# TNY275_REMOTE_677.net
KiCad netlist of a schematic drawn in Altium Designer
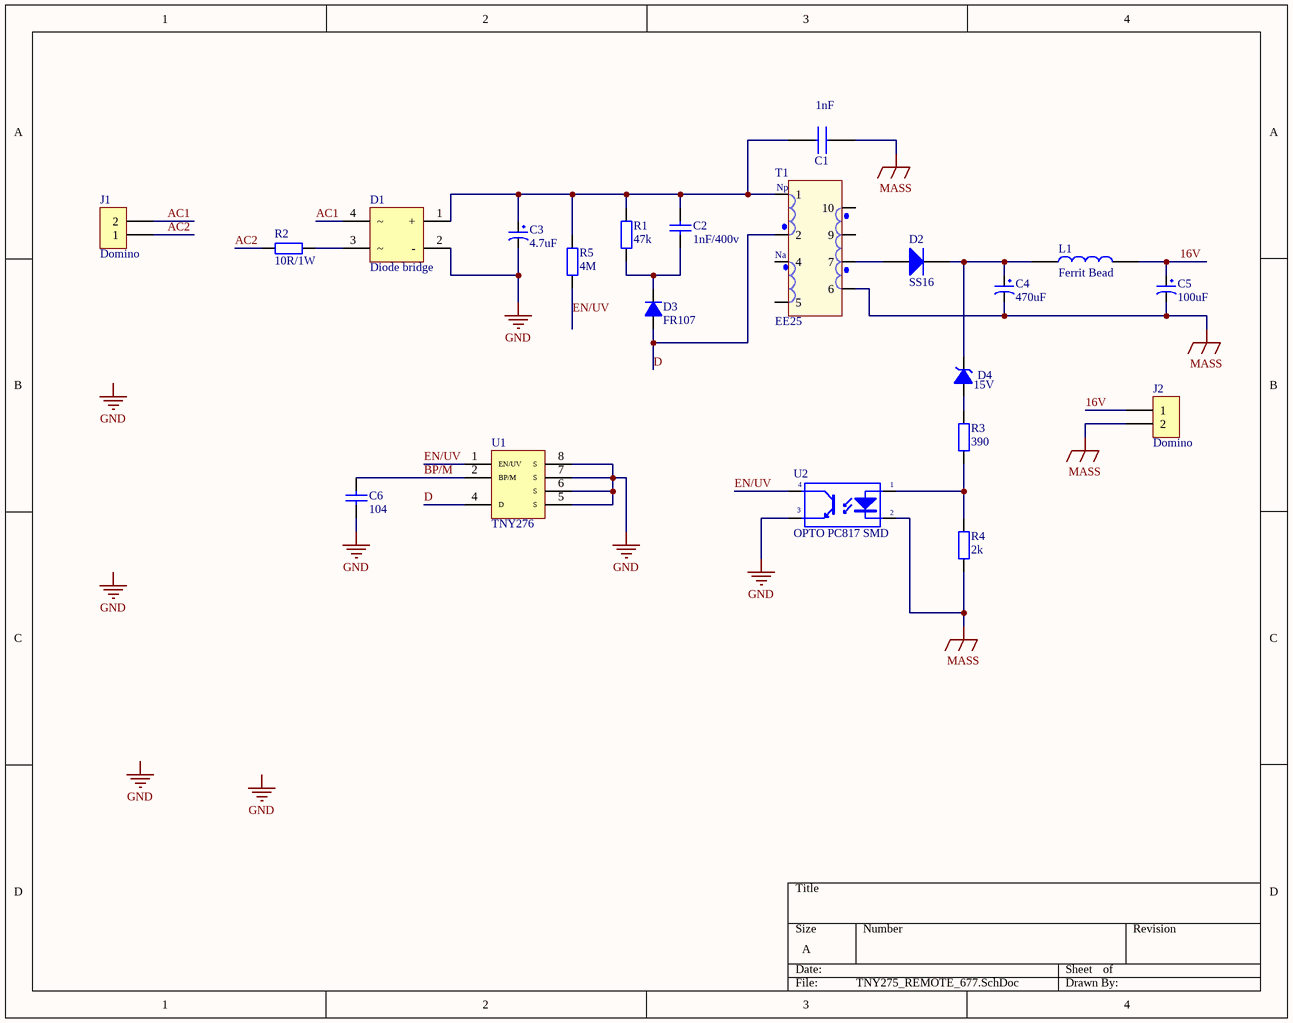
[diagram p0: TNY275_REMOTE_677.SchDoc]

(export (version "E")
  (design (tool "Eeschema 10.0.6"))
  (components
    (comp (ref "C1")
      (value "1nF")
      (footprint "toan:Tenta capacitor")
      (description "...nF +/-10% 275VAC 15 Through Hole Suppression Capacitors")
      (fields (field (name "MANUFACTURER_PART_NUMBER") "MEX104K275A"))
      (libsource (lib "Tenta capacitor") (part "Tenta capacitor"))
    )
    (comp (ref "C2")
      (value "1nF/400v")
      (footprint "tu tantalum dip5.08")
      (description "tụ cao áp Cắm")
      (libsource (lib "Altium_Lib_by_KhueNguyenCreator") (part "Tu tantalum 10nF DIP5.08"))
    )
    (comp (ref "C3")
      (value "4.7uF")
      (footprint "tu hoa 8mm")
      (description "Cắm")
      (libsource (lib "Altium_Lib_by_KhueNguyenCreator") (part "Tu Hoa 4.7uF 400V 8x12"))
    )
    (comp (ref "C4")
      (value "470uF")
      (footprint "tu hoa 8mm")
      (description "Cắm")
      (libsource (lib "Altium_Lib_by_KhueNguyenCreator") (part "Tu Hoa 470uF 25V 8x13"))
    )
    (comp (ref "C5")
      (value "100uF")
      (footprint "tu hoa 5mm")
      (description "Cắm")
      (libsource (lib "Altium_Lib_by_KhueNguyenCreator") (part "Tu Hoa 100uF 25V 6x11"))
    )
    (comp (ref "C6")
      (value "104")
      (footprint "tu 0805")
      (description "Dán")
      (libsource (lib "Altium_Lib_by_KhueNguyenCreator") (part "Tu 0805 104 50V 10%"))
    )
    (comp (ref "D1")
      (value "Diode bridge")
      (footprint "DS207S:DS207S")
      (description "Diode cau 2A 1000V")
      (libsource (lib "DS207S") (part "DS207S"))
    )
    (comp (ref "D2")
      (value "SS16")
      (footprint "DIODE SMA")
      (description "Dán")
      (libsource (lib "Altium_Lib_by_KhueNguyenCreator") (part "Diode SS14 ( 1N5819)"))
    )
    (comp (ref "D3")
      (value "FR107")
      (footprint "DIODE 2A")
      (description "Cắm")
      (libsource (lib "Altium_Lib_by_KhueNguyenCreator") (part "Diode FR207"))
    )
    (comp (ref "D4")
      (value "15V")
      (footprint "DZ1A")
      (description "Diode Zenner")
      (libsource (lib "syhaunguyen") (part "DZ"))
    )
    (comp (ref "J1")
      (value "Domino")
      (footprint "Domino:Domino")
      (description "Domino 5.04mm")
      (libsource (lib "") (part "Domino_1"))
    )
    (comp (ref "J2")
      (value "Domino")
      (footprint "Domino:Domino")
      (description "Domino 5.04mm")
      (libsource (lib "Domino") (part "Domino"))
    )
    (comp (ref "L1")
      (value "Ferrit Bead")
      (footprint "Cuon Cam:CUON CAM")
      (description "Cuộn lọc RH3.5x9x0.8 Cắm")
      (libsource (lib "Altium_Lib_by_KhueNguyenCreator") (part "CUON CAM 470uH DIP"))
    )
    (comp (ref "R1")
      (value "47k")
      (footprint "tro smd 0805")
      (description "Dán")
      (libsource (lib "Altium_Lib_by_KhueNguyenCreator") (part "Tro 0805 5% 47k"))
    )
    (comp (ref "R2")
      (value "10R/1W")
      (footprint "tro vach 1w")
      (description "Cắm")
      (libsource (lib "Altium_Lib_by_KhueNguyenCreator") (part "Tro Vach 1W 5% 3.3R"))
    )
    (comp (ref "R3")
      (value "390")
      (footprint "tro smd 0805")
      (description "Dán")
      (libsource (lib "Altium_Lib_by_KhueNguyenCreator") (part "Tro 0805 5% 2.2k"))
    )
    (comp (ref "R4")
      (value "2k")
      (footprint "tro smd 0805")
      (description "Dán")
      (libsource (lib "Altium_Lib_by_KhueNguyenCreator") (part "Tro 0805 5% 220R"))
    )
    (comp (ref "R5")
      (value "4M")
      (footprint "tro smd 0805")
      (description "Dán")
      (libsource (lib "Altium_Lib_by_KhueNguyenCreator") (part "Tro 0805 5% 47k"))
    )
    (comp (ref "T1")
      (value "EE25")
      (footprint "toan:EE25_0.5")
      (description "EE25 10PIN")
      (libsource (lib "EE25") (part "EE25"))
    )
    (comp (ref "U1")
      (value "TNY276")
      (footprint "TNY27X DIP:PCBComponent_1")
      (description "TNY274-280\r\nTinySwitch-III Family - DIP/PDIP-8C")
      (libsource (lib "TNY27X-DIP") (part "TNY276"))
    )
    (comp (ref "U2")
      (value "OPTO PC817 SMD")
      (footprint "SOP4")
      (description "Single Opto")
      (libsource (lib "Altium_Lib_by_KhueNguyenCreator") (part "OPTO PC817 SMD"))
    )
  )
  (nets
    (net (code "1") (name "/16V") (class "Default")
      (node (ref "C5") (pin "1") (pinfunction "1_1") (pintype "passive"))
      (node (ref "J2") (pin "1") (pinfunction "1_1") (pintype "passive"))
      (node (ref "L1") (pin "2") (pinfunction "2_2") (pintype "passive"))
    )
    (net (code "2") (name "/AC1") (class "Default")
      (node (ref "D1") (pin "4") (pinfunction "~_4") (pintype "passive"))
      (node (ref "J1") (pin "2") (pinfunction "2_2") (pintype "passive"))
    )
    (net (code "3") (name "/AC2") (class "Default")
      (node (ref "J1") (pin "1") (pinfunction "1_1") (pintype "passive"))
      (node (ref "R2") (pin "1") (pinfunction "1_1") (pintype "passive"))
    )
    (net (code "4") (name "/BP{slash}M") (class "Default")
      (node (ref "C6") (pin "1") (pinfunction "1_1") (pintype "passive"))
      (node (ref "U1") (pin "2") (pinfunction "BP/M_2") (pintype "passive"))
    )
    (net (code "5") (name "/D") (class "Default")
      (node (ref "D3") (pin "1") (pinfunction "A_1") (pintype "passive"))
      (node (ref "T1") (pin "2") (pinfunction "2_2") (pintype "passive"))
      (node (ref "U1") (pin "4") (pinfunction "D_4") (pintype "passive"))
    )
    (net (code "6") (name "/EN{slash}UV") (class "Default")
      (node (ref "R5") (pin "1") (pinfunction "1_1") (pintype "passive"))
      (node (ref "U1") (pin "1") (pinfunction "EN/UV_1") (pintype "passive"))
      (node (ref "U2") (pin "4") (pinfunction "C_4") (pintype "passive"))
    )
    (net (code "7") (name "GND") (class "Default")
      (node (ref "C3") (pin "2") (pinfunction "2_2") (pintype "passive"))
      (node (ref "C6") (pin "2") (pinfunction "2_2") (pintype "passive"))
      (node (ref "D1") (pin "2") (pinfunction "-_2") (pintype "passive"))
      (node (ref "U1") (pin "5") (pinfunction "S_5") (pintype "passive"))
      (node (ref "U1") (pin "6") (pinfunction "S_6") (pintype "passive"))
      (node (ref "U1") (pin "7") (pinfunction "S_7") (pintype "passive"))
      (node (ref "U1") (pin "8") (pinfunction "S_8") (pintype "passive"))
      (node (ref "U2") (pin "3") (pinfunction "E_3") (pintype "passive"))
    )
    (net (code "8") (name "MASS") (class "Default")
      (node (ref "C1") (pin "2") (pinfunction "2_2") (pintype "passive"))
      (node (ref "C4") (pin "2") (pinfunction "2_2") (pintype "passive"))
      (node (ref "C5") (pin "2") (pinfunction "2_2") (pintype "passive"))
      (node (ref "J2") (pin "2") (pinfunction "2_2") (pintype "passive"))
      (node (ref "R4") (pin "1") (pinfunction "1_1") (pintype "passive"))
      (node (ref "T1") (pin "6") (pinfunction "6_6") (pintype "passive"))
      (node (ref "U2") (pin "2") (pinfunction "K_2") (pintype "passive"))
    )
    (net (code "9") (name "Net-(D1-+)") (class "Default")
      (node (ref "C1") (pin "1") (pinfunction "1_1") (pintype "passive"))
      (node (ref "C2") (pin "1") (pinfunction "1_1") (pintype "passive"))
      (node (ref "C3") (pin "1") (pinfunction "1_1") (pintype "passive"))
      (node (ref "D1") (pin "1") (pinfunction "+_1") (pintype "passive"))
      (node (ref "R1") (pin "2") (pinfunction "2_2") (pintype "passive"))
      (node (ref "R5") (pin "2") (pinfunction "2_2") (pintype "passive"))
      (node (ref "T1") (pin "1") (pinfunction "1_1") (pintype "passive"))
    )
    (net (code "10") (name "Net-(D1-~-Pad3)") (class "Default")
      (node (ref "D1") (pin "3") (pinfunction "~_3") (pintype "passive"))
      (node (ref "R2") (pin "2") (pinfunction "2_2") (pintype "passive"))
    )
    (net (code "11") (name "Net-(D2-A)") (class "Default")
      (node (ref "D2") (pin "1") (pinfunction "A_1") (pintype "passive"))
      (node (ref "T1") (pin "7") (pinfunction "7_7") (pintype "passive"))
    )
    (net (code "12") (name "Net-(D2-K)") (class "Default")
      (node (ref "C4") (pin "1") (pinfunction "1_1") (pintype "passive"))
      (node (ref "D2") (pin "2") (pinfunction "K_2") (pintype "passive"))
      (node (ref "D4") (pin "2") (pinfunction "K_2") (pintype "passive"))
      (node (ref "L1") (pin "1") (pinfunction "1_1") (pintype "passive"))
    )
    (net (code "13") (name "Net-(D3-K)") (class "Default")
      (node (ref "C2") (pin "2") (pinfunction "2_2") (pintype "passive"))
      (node (ref "D3") (pin "2") (pinfunction "K_2") (pintype "passive"))
      (node (ref "R1") (pin "1") (pinfunction "1_1") (pintype "passive"))
    )
    (net (code "14") (name "Net-(D4-A)") (class "Default")
      (node (ref "D4") (pin "1") (pinfunction "A_1") (pintype "passive"))
      (node (ref "R3") (pin "2") (pinfunction "2_2") (pintype "passive"))
    )
    (net (code "15") (name "Net-(U2-A)") (class "Default")
      (node (ref "R3") (pin "1") (pinfunction "1_1") (pintype "passive"))
      (node (ref "R4") (pin "2") (pinfunction "2_2") (pintype "passive"))
      (node (ref "U2") (pin "1") (pinfunction "A_1") (pintype "passive"))
    )
    (net (code "16") (name "unconnected-(T1-Pad4)") (class "Default")
      (node (ref "T1") (pin "4") (pinfunction "4_4") (pintype "passive"))
    )
    (net (code "17") (name "unconnected-(T1-Pad5)") (class "Default")
      (node (ref "T1") (pin "5") (pinfunction "5_5") (pintype "passive"))
    )
    (net (code "18") (name "unconnected-(T1-Pad9)") (class "Default")
      (node (ref "T1") (pin "9") (pinfunction "9_9") (pintype "passive"))
    )
    (net (code "19") (name "unconnected-(T1-Pad10)") (class "Default")
      (node (ref "T1") (pin "10") (pinfunction "10_10") (pintype "passive"))
    )
  )
)
